# Buttons.net
KiCad netlist of a schematic drawn in EAGLE
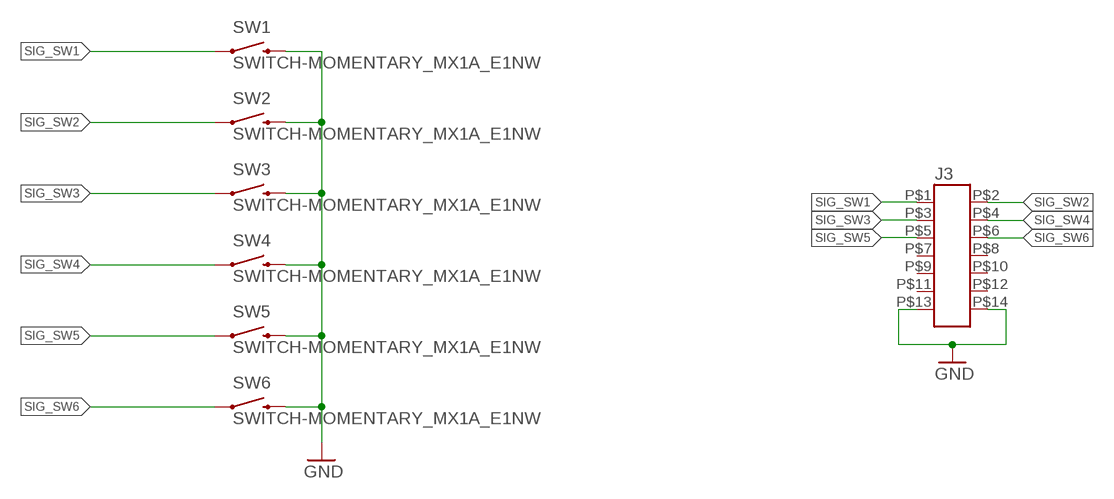
[diagram p0: schematic, sheet 1]

(export (version "E")
  (design (tool "Eeschema 10.0.6"))
  (components
    (comp (ref "J3")
      (value "HEADER-2X7")
      (footprint "eagle-import:3M-3000SERIES-HEADER-RIGHTANGLE")
      (libsource (lib "eagle-import") (part "HEADER-2X7"))
    )
    (comp (ref "SW1")
      (value "SWITCH-MOMENTARY_MX1A_E1NW")
      (footprint "eagle-import:CHERRY_MX1A_E1NW")
      (libsource (lib "eagle-import") (part "SWITCH-MOMENTARY_MX1A_E1NW"))
    )
    (comp (ref "SW2")
      (value "SWITCH-MOMENTARY_MX1A_E1NW")
      (footprint "eagle-import:CHERRY_MX1A_E1NW")
      (libsource (lib "eagle-import") (part "SWITCH-MOMENTARY_MX1A_E1NW"))
    )
    (comp (ref "SW3")
      (value "SWITCH-MOMENTARY_MX1A_E1NW")
      (footprint "eagle-import:CHERRY_MX1A_E1NW")
      (libsource (lib "eagle-import") (part "SWITCH-MOMENTARY_MX1A_E1NW"))
    )
    (comp (ref "SW4")
      (value "SWITCH-MOMENTARY_MX1A_E1NW")
      (footprint "eagle-import:CHERRY_MX1A_E1NW")
      (libsource (lib "eagle-import") (part "SWITCH-MOMENTARY_MX1A_E1NW"))
    )
    (comp (ref "SW5")
      (value "SWITCH-MOMENTARY_MX1A_E1NW")
      (footprint "eagle-import:CHERRY_MX1A_E1NW")
      (libsource (lib "eagle-import") (part "SWITCH-MOMENTARY_MX1A_E1NW"))
    )
    (comp (ref "SW6")
      (value "SWITCH-MOMENTARY_MX1A_E1NW")
      (footprint "eagle-import:CHERRY_MX1A_E1NW")
      (libsource (lib "eagle-import") (part "SWITCH-MOMENTARY_MX1A_E1NW"))
    )
  )
  (nets
    (net (code "1") (name "GND") (class "Default")
      (node (ref "J3") (pin "P$13") (pinfunction "13_P$13") (pintype "bidirectional"))
      (node (ref "J3") (pin "P$14") (pinfunction "14_P$14") (pintype "bidirectional"))
      (node (ref "SW1") (pin "P$2") (pinfunction "2_P$2") (pintype "passive"))
      (node (ref "SW2") (pin "P$2") (pinfunction "2_P$2") (pintype "passive"))
      (node (ref "SW3") (pin "P$2") (pinfunction "2_P$2") (pintype "passive"))
      (node (ref "SW4") (pin "P$2") (pinfunction "2_P$2") (pintype "passive"))
      (node (ref "SW5") (pin "P$2") (pinfunction "2_P$2") (pintype "passive"))
      (node (ref "SW6") (pin "P$2") (pinfunction "2_P$2") (pintype "passive"))
    )
    (net (code "2") (name "SIG_SW1") (class "Default")
      (node (ref "J3") (pin "P$1") (pinfunction "1_P$1") (pintype "bidirectional"))
      (node (ref "SW1") (pin "P$1") (pinfunction "1_P$1") (pintype "passive"))
    )
    (net (code "3") (name "SIG_SW2") (class "Default")
      (node (ref "J3") (pin "P$2") (pinfunction "2_P$2") (pintype "bidirectional"))
      (node (ref "SW2") (pin "P$1") (pinfunction "1_P$1") (pintype "passive"))
    )
    (net (code "4") (name "SIG_SW3") (class "Default")
      (node (ref "J3") (pin "P$3") (pinfunction "3_P$3") (pintype "bidirectional"))
      (node (ref "SW3") (pin "P$1") (pinfunction "1_P$1") (pintype "passive"))
    )
    (net (code "5") (name "SIG_SW4") (class "Default")
      (node (ref "J3") (pin "P$4") (pinfunction "4_P$4") (pintype "bidirectional"))
      (node (ref "SW4") (pin "P$1") (pinfunction "1_P$1") (pintype "passive"))
    )
    (net (code "6") (name "SIG_SW5") (class "Default")
      (node (ref "J3") (pin "P$5") (pinfunction "5_P$5") (pintype "bidirectional"))
      (node (ref "SW5") (pin "P$1") (pinfunction "1_P$1") (pintype "passive"))
    )
    (net (code "7") (name "SIG_SW6") (class "Default")
      (node (ref "J3") (pin "P$6") (pinfunction "6_P$6") (pintype "bidirectional"))
      (node (ref "SW6") (pin "P$1") (pinfunction "1_P$1") (pintype "passive"))
    )
    (net (code "8") (name "unconnected-(J3-7-PadP$7)") (class "Default")
      (node (ref "J3") (pin "P$7") (pinfunction "7_P$7") (pintype "bidirectional"))
    )
    (net (code "9") (name "unconnected-(J3-8-PadP$8)") (class "Default")
      (node (ref "J3") (pin "P$8") (pinfunction "8_P$8") (pintype "bidirectional"))
    )
    (net (code "10") (name "unconnected-(J3-9-PadP$9)") (class "Default")
      (node (ref "J3") (pin "P$9") (pinfunction "9_P$9") (pintype "bidirectional"))
    )
    (net (code "11") (name "unconnected-(J3-10-PadP$10)") (class "Default")
      (node (ref "J3") (pin "P$10") (pinfunction "10_P$10") (pintype "bidirectional"))
    )
    (net (code "12") (name "unconnected-(J3-11-PadP$11)") (class "Default")
      (node (ref "J3") (pin "P$11") (pinfunction "11_P$11") (pintype "bidirectional"))
    )
    (net (code "13") (name "unconnected-(J3-12-PadP$12)") (class "Default")
      (node (ref "J3") (pin "P$12") (pinfunction "12_P$12") (pintype "bidirectional"))
    )
  )
)
